# selfbus_dap_debugger.net
KiCad netlist of a schematic drawn in EAGLE
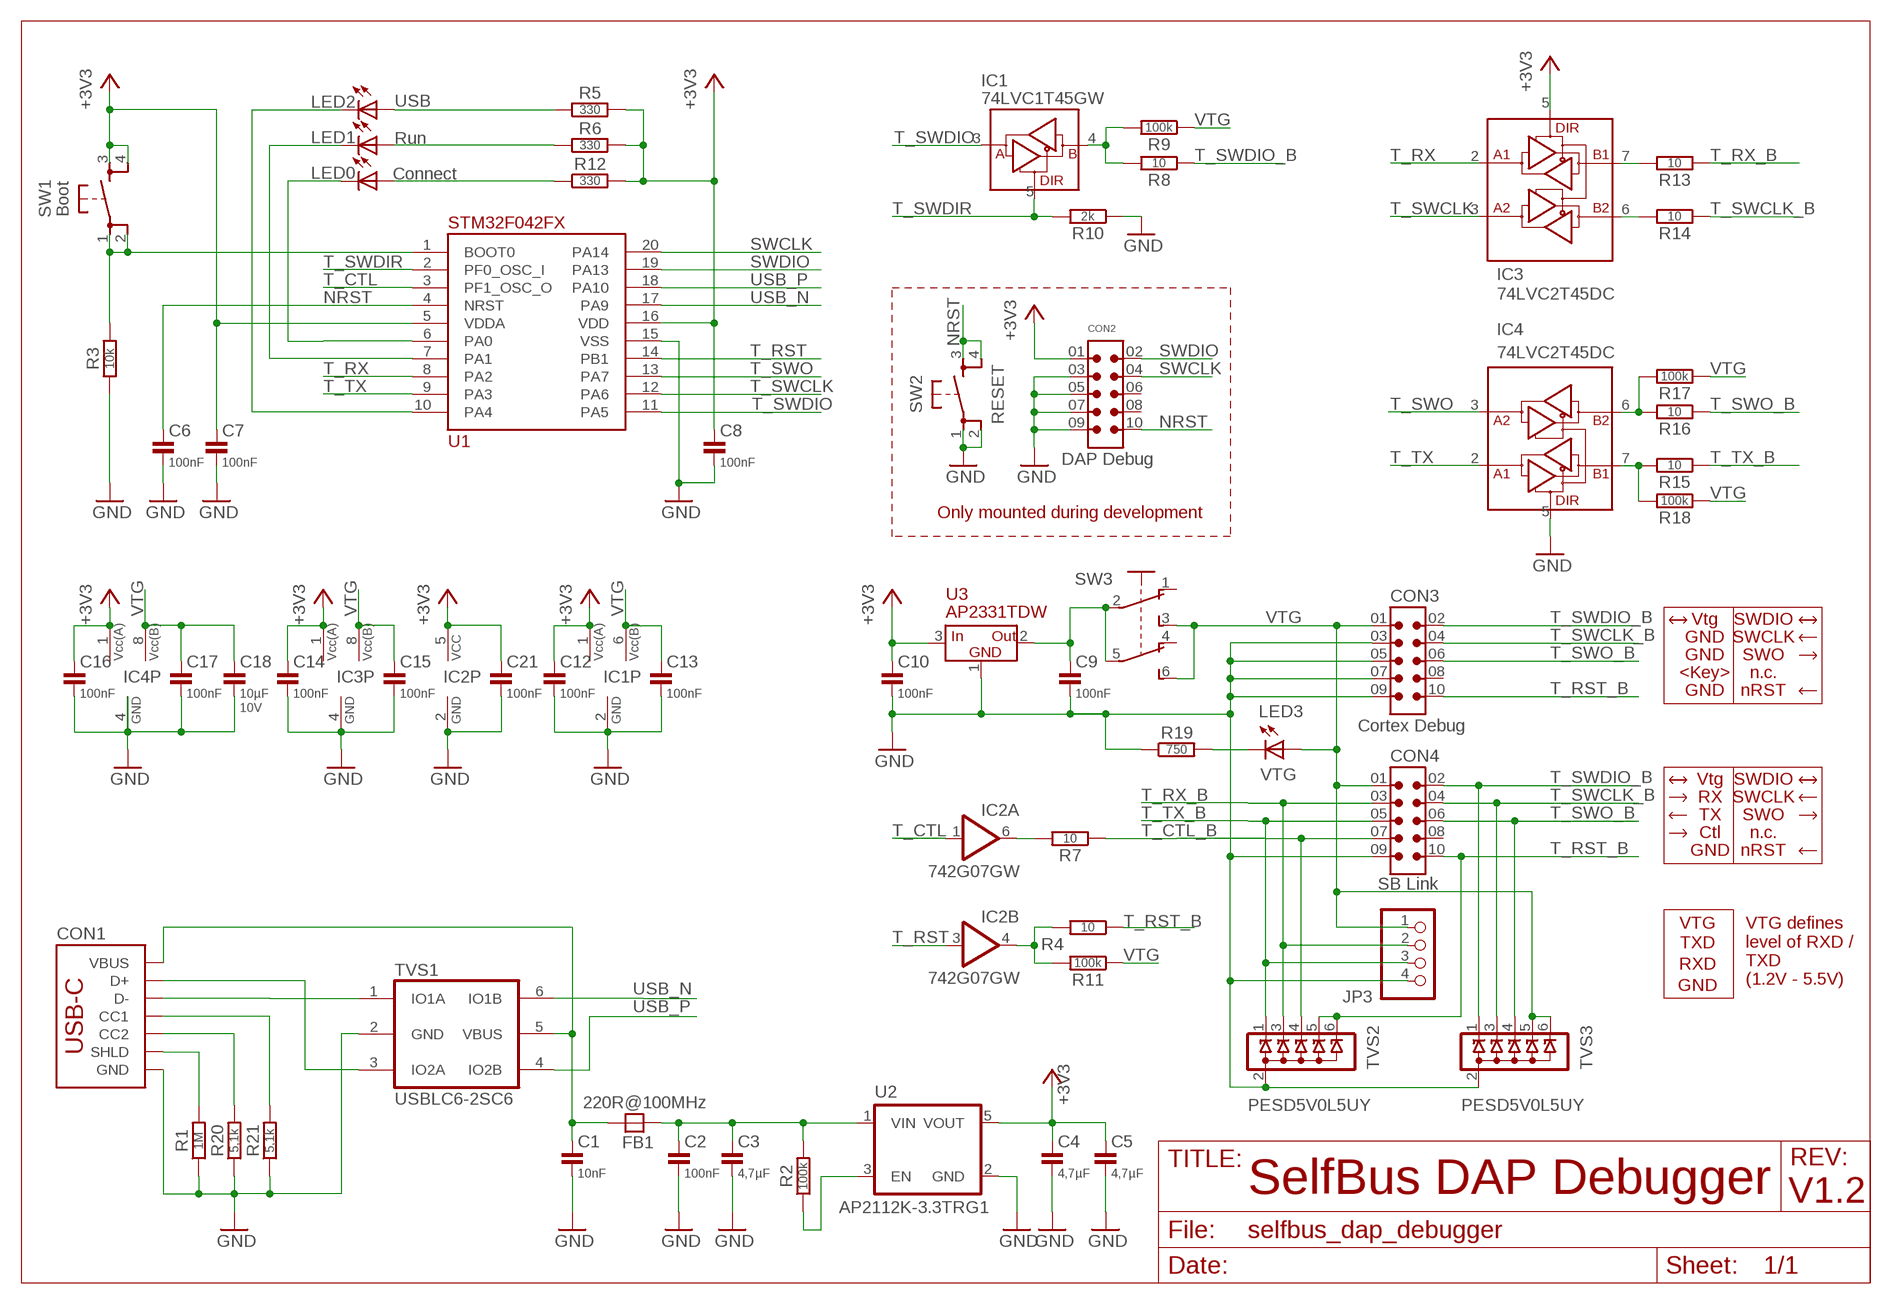
[diagram p0: schematic, sheet 1]

(export (version "E")
  (design (tool "Eeschema 10.0.6"))
  (components
    (comp (ref "C1")
      (value "10nF")
      (footprint "eagle-import:C0805")
      (libsource (lib "eagle-import") (part "C-EUC0805"))
    )
    (comp (ref "C2")
      (value "100nF")
      (footprint "eagle-import:C0805")
      (libsource (lib "eagle-import") (part "C-EUC0805"))
    )
    (comp (ref "C3")
      (value "4,7µF")
      (footprint "eagle-import:C0805")
      (libsource (lib "eagle-import") (part "C-EUC0805"))
    )
    (comp (ref "C4")
      (value "4,7µF")
      (footprint "eagle-import:C0805")
      (libsource (lib "eagle-import") (part "C-EUC0805"))
    )
    (comp (ref "C5")
      (value "4,7µF")
      (footprint "eagle-import:C0805")
      (libsource (lib "eagle-import") (part "C-EUC0805"))
    )
    (comp (ref "C6")
      (value "100nF")
      (footprint "eagle-import:C0805")
      (libsource (lib "eagle-import") (part "C-EUC0805"))
    )
    (comp (ref "C7")
      (value "100nF")
      (footprint "eagle-import:C0805")
      (libsource (lib "eagle-import") (part "C-EUC0805"))
    )
    (comp (ref "C8")
      (value "100nF")
      (footprint "eagle-import:C0805")
      (libsource (lib "eagle-import") (part "C-EUC0805"))
    )
    (comp (ref "C9")
      (value "100nF")
      (footprint "eagle-import:C0805")
      (libsource (lib "eagle-import") (part "C-EUC0805"))
    )
    (comp (ref "C10")
      (value "100nF")
      (footprint "eagle-import:C0805")
      (libsource (lib "eagle-import") (part "C-EUC0805"))
    )
    (comp (ref "C12")
      (value "100nF")
      (footprint "eagle-import:C0805")
      (libsource (lib "eagle-import") (part "C-EUC0805"))
    )
    (comp (ref "C13")
      (value "100nF")
      (footprint "eagle-import:C0805")
      (libsource (lib "eagle-import") (part "C-EUC0805"))
    )
    (comp (ref "C14")
      (value "100nF")
      (footprint "eagle-import:C0805")
      (libsource (lib "eagle-import") (part "C-EUC0805"))
    )
    (comp (ref "C15")
      (value "100nF")
      (footprint "eagle-import:C0805")
      (libsource (lib "eagle-import") (part "C-EUC0805"))
    )
    (comp (ref "C16")
      (value "100nF")
      (footprint "eagle-import:C0805")
      (libsource (lib "eagle-import") (part "C-EUC0805"))
    )
    (comp (ref "C17")
      (value "100nF")
      (footprint "eagle-import:C0805")
      (libsource (lib "eagle-import") (part "C-EUC0805"))
    )
    (comp (ref "C18")
      (value "10µF")
      (footprint "eagle-import:C0805")
      (fields (field (name "VOLTAGE") "10V"))
      (libsource (lib "eagle-import") (part "C-EUC0805"))
    )
    (comp (ref "C21")
      (value "100nF")
      (footprint "eagle-import:C0805")
      (libsource (lib "eagle-import") (part "C-EUC0805"))
    )
    (comp (ref "CON1")
      (value "XKB U262-161N-4BVC11")
      (footprint "eagle-import:USB-C-16P-2LAYER-PADS")
      (libsource (lib "eagle-import") (part "USB_C_2-LAYER_PADS"))
    )
    (comp (ref "CON2")
      (value "SHF-105-01-X-D-TH")
      (footprint "eagle-import:SAMTEC_SHF-105-01-X-D-TH")
      (libsource (lib "eagle-import") (part "SHF-105-01-X-D-TH"))
    )
    (comp (ref "CON3")
      (value "SHF-105-01-X-D-TH")
      (footprint "eagle-import:SAMTEC_SHF-105-01-X-D-TH")
      (libsource (lib "eagle-import") (part "SHF-105-01-X-D-TH"))
    )
    (comp (ref "CON4")
      (value "SAMTEC-LTMM-105-02-T-D")
      (footprint "eagle-import:SAMTEC-LTMM-105-02-T-D")
      (libsource (lib "eagle-import") (part "SAMTEC-LTMM-105-02-T-D"))
    )
    (comp (ref "FB1")
      (value "220R@100MHz")
      (footprint "eagle-import:FB0805")
      (fields (field (name "PART#") "MPZ2012S221ATD25"))
      (libsource (lib "eagle-import") (part "FB"))
    )
    (comp (ref "IC1")
      (value "74LVC1T45GW")
      (footprint "eagle-import:SOT363")
      (fields
        (field (name "LCSC#") "C478004")
        (field (name "LCSC#2") "C548484")
        (field (name "LCSC#3") "C9382")
        (field (name "MOUSER#") "771-74LVC1T45GW125")
        (field (name "MOUSER#2") "771-74LVC1T45GWQ100H")
        (field (name "MOUSER#3") "595-74LVC1T45QDCKRQ1")
        (field (name "PART#") "74LVC1T45GW,125")
        (field (name "PART#2") "74LVC1T45GW-Q100H")
        (field (name "PART#3") "SN74LVC1T45DCKR")
        (field (name "PART_MFR") "NXP")
        (field (name "PART_MFR2") "NXP")
        (field (name "PART_MFR3") "TI")
      )
      (libsource (lib "eagle-import") (part "741T45GWLVC"))
    )
    (comp (ref "IC2")
      (value "742G07GW")
      (footprint "eagle-import:SOT363")
      (fields
        (field (name "LCSC#") "C24478")
        (field (name "PART#") "74LVC2G07GW,125")
        (field (name "PART_MFR") "NXP")
      )
      (libsource (lib "eagle-import") (part "742G07GW"))
    )
    (comp (ref "IC3")
      (value "74LVC2T45DC")
      (footprint "eagle-import:VSSOP8(0.5)")
      (fields
        (field (name "LCSC#") "C15741")
        (field (name "LCSC#2") "C139524")
        (field (name "MOUSER#") "595-SN74LVC2T45DCUT")
        (field (name "MOUSER#2") "771-74LVCH2T45DC125")
        (field (name "PART#") "SN74LVC2T45DCU")
        (field (name "PART#2") "74LVCH2T45DC,125")
        (field (name "PART_MFR") "TI")
        (field (name "PART_MFR2") "NXP")
      )
      (libsource (lib "eagle-import") (part "742T45DCLVC"))
    )
    (comp (ref "IC4")
      (value "74LVC2T45DC")
      (footprint "eagle-import:VSSOP8(0.5)")
      (libsource (lib "eagle-import") (part "742T45DCLVC"))
    )
    (comp (ref "JP3")
      (value "PINHD-1X4")
      (footprint "eagle-import:1X04")
      (libsource (lib "eagle-import") (part "PINHD-1X4"))
    )
    (comp (ref "LED0")
      (value "Connect")
      (footprint "eagle-import:LED_3MM_GREEN")
      (libsource (lib "eagle-import") (part "LED_3MM(T1)_GREEN"))
    )
    (comp (ref "LED1")
      (value "Run")
      (footprint "eagle-import:LED_3MM_YELLOW")
      (libsource (lib "eagle-import") (part "LED_3MM(T1)_YELLOW"))
    )
    (comp (ref "LED2")
      (value "USB")
      (footprint "eagle-import:LED_3MM_GREEN")
      (libsource (lib "eagle-import") (part "LED_3MM(T1)_GREEN"))
    )
    (comp (ref "LED3")
      (value "VTG")
      (footprint "eagle-import:LED_3MM_RED")
      (libsource (lib "eagle-import") (part "LED_3MM(T1)_RED"))
    )
    (comp (ref "R1")
      (value "1M")
      (footprint "eagle-import:R0805")
      (libsource (lib "eagle-import") (part "R-EU_R0805"))
    )
    (comp (ref "R2")
      (value "100k")
      (footprint "eagle-import:R0805")
      (libsource (lib "eagle-import") (part "R-EU_R0805"))
    )
    (comp (ref "R3")
      (value "10k")
      (footprint "eagle-import:R0805")
      (libsource (lib "eagle-import") (part "R-EU_R0805"))
    )
    (comp (ref "R4")
      (value "10")
      (footprint "eagle-import:R0805")
      (libsource (lib "eagle-import") (part "R-EU_R0805"))
    )
    (comp (ref "R5")
      (value "330")
      (footprint "eagle-import:R0805")
      (libsource (lib "eagle-import") (part "R-EU_R0805"))
    )
    (comp (ref "R6")
      (value "330")
      (footprint "eagle-import:R0805")
      (libsource (lib "eagle-import") (part "R-EU_R0805"))
    )
    (comp (ref "R7")
      (value "10")
      (footprint "eagle-import:R0805")
      (libsource (lib "eagle-import") (part "R-EU_R0805"))
    )
    (comp (ref "R8")
      (value "10")
      (footprint "eagle-import:R0805")
      (libsource (lib "eagle-import") (part "R-EU_R0805"))
    )
    (comp (ref "R9")
      (value "100k")
      (footprint "eagle-import:R0805")
      (libsource (lib "eagle-import") (part "R-EU_R0805"))
    )
    (comp (ref "R10")
      (value "2k")
      (footprint "eagle-import:R0805")
      (libsource (lib "eagle-import") (part "R-EU_R0805"))
    )
    (comp (ref "R11")
      (value "100k")
      (footprint "eagle-import:R0805")
      (libsource (lib "eagle-import") (part "R-EU_R0805"))
    )
    (comp (ref "R12")
      (value "330")
      (footprint "eagle-import:R0805")
      (libsource (lib "eagle-import") (part "R-EU_R0805"))
    )
    (comp (ref "R13")
      (value "10")
      (footprint "eagle-import:R0805")
      (libsource (lib "eagle-import") (part "R-EU_R0805"))
    )
    (comp (ref "R14")
      (value "10")
      (footprint "eagle-import:R0805")
      (libsource (lib "eagle-import") (part "R-EU_R0805"))
    )
    (comp (ref "R15")
      (value "10")
      (footprint "eagle-import:R0805")
      (libsource (lib "eagle-import") (part "R-EU_R0805"))
    )
    (comp (ref "R16")
      (value "10")
      (footprint "eagle-import:R0805")
      (libsource (lib "eagle-import") (part "R-EU_R0805"))
    )
    (comp (ref "R17")
      (value "100k")
      (footprint "eagle-import:R0805")
      (libsource (lib "eagle-import") (part "R-EU_R0805"))
    )
    (comp (ref "R18")
      (value "100k")
      (footprint "eagle-import:R0805")
      (libsource (lib "eagle-import") (part "R-EU_R0805"))
    )
    (comp (ref "R19")
      (value "750")
      (footprint "eagle-import:R0805")
      (libsource (lib "eagle-import") (part "R-EU_R0805"))
    )
    (comp (ref "R20")
      (value "5,1k")
      (footprint "eagle-import:R0805")
      (libsource (lib "eagle-import") (part "R-EU_R0805"))
    )
    (comp (ref "R21")
      (value "5,1k")
      (footprint "eagle-import:R0805")
      (libsource (lib "eagle-import") (part "R-EU_R0805"))
    )
    (comp (ref "SW1")
      (value "BOOT")
      (footprint "eagle-import:TACT_SWITCH_6X6_SNAP-IN_17")
      (fields (field (name "PART#") "SKHHDHA010"))
      (libsource (lib "eagle-import") (part "ALPS_SKHHDHA010"))
    )
    (comp (ref "SW2")
      (value "RESET")
      (footprint "eagle-import:TACT_SWITCH_6X6_SNAP-IN_17")
      (fields (field (name "PART#") "SKHHDHA010"))
      (libsource (lib "eagle-import") (part "ALPS_SKHHDHA010"))
    )
    (comp (ref "SW3")
      (value "XKB7070-Z")
      (footprint "eagle-import:XKB7070")
      (libsource (lib "eagle-import") (part "XKB7070-Z"))
    )
    (comp (ref "TVS1")
      (value "USBLC6-2SC6")
      (footprint "eagle-import:SOT-23-6L")
      (libsource (lib "eagle-import") (part "USBLC6-2SC6"))
    )
    (comp (ref "TVS2")
      (value "PESD5V0L5UY")
      (footprint "eagle-import:SOT363")
      (libsource (lib "eagle-import") (part "PESD5V0L5UY"))
    )
    (comp (ref "TVS3")
      (value "PESD5V0L5UY")
      (footprint "eagle-import:SOT363")
      (libsource (lib "eagle-import") (part "PESD5V0L5UY"))
    )
    (comp (ref "U1")
      (value "STM32F042FX")
      (footprint "eagle-import:TSSOP20")
      (fields (field (name "PART#") "STM32F042F4P6"))
      (libsource (lib "eagle-import") (part "STM32F042FX"))
    )
    (comp (ref "U2")
      (value "AP2112K-3.3TRG1")
      (footprint "eagle-import:SOT23-5")
      (libsource (lib "eagle-import") (part "AP2112K-3.3TRG1"))
    )
    (comp (ref "U3")
      (value "AP2331TDW")
      (footprint "eagle-import:SC59")
      (fields (field (name "PART#") "AP2331W-7"))
      (libsource (lib "eagle-import") (part "AP2331TDW"))
    )
  )
  (nets
    (net (code "1") (name "+3V3") (class "Default")
      (node (ref "C10") (pin "1") (pinfunction "1_1") (pintype "passive"))
      (node (ref "C12") (pin "1") (pinfunction "1_1") (pintype "passive"))
      (node (ref "C14") (pin "1") (pinfunction "1_1") (pintype "passive"))
      (node (ref "C16") (pin "1") (pinfunction "1_1") (pintype "passive"))
      (node (ref "C21") (pin "1") (pinfunction "1_1") (pintype "passive"))
      (node (ref "C4") (pin "1") (pinfunction "1_1") (pintype "passive"))
      (node (ref "C5") (pin "1") (pinfunction "1_1") (pintype "passive"))
      (node (ref "C7") (pin "1") (pinfunction "1_1") (pintype "passive"))
      (node (ref "C8") (pin "1") (pinfunction "1_1") (pintype "passive"))
      (node (ref "CON2") (pin "01") (pinfunction "1_01") (pintype "passive"))
      (node (ref "IC1") (pin "1") (pinfunction "VCC(A)_1") (pintype "power_in"))
      (node (ref "IC2") (pin "5") (pinfunction "VCC_5") (pintype "power_in"))
      (node (ref "IC3") (pin "1") (pinfunction "VCC(A)_1") (pintype "power_in"))
      (node (ref "IC3") (pin "5") (pinfunction "DIR_5") (pintype "input"))
      (node (ref "IC4") (pin "1") (pinfunction "VCC(A)_1") (pintype "power_in"))
      (node (ref "R12") (pin "2") (pinfunction "2_2") (pintype "passive"))
      (node (ref "R5") (pin "2") (pinfunction "2_2") (pintype "passive"))
      (node (ref "R6") (pin "2") (pinfunction "2_2") (pintype "passive"))
      (node (ref "SW1") (pin "3") (pinfunction "3_3") (pintype "passive"))
      (node (ref "SW1") (pin "4") (pinfunction "4_4") (pintype "passive"))
      (node (ref "U1") (pin "16") (pinfunction "VDD_16") (pintype "power_in"))
      (node (ref "U1") (pin "5") (pinfunction "VDDA_5") (pintype "power_in"))
      (node (ref "U2") (pin "5") (pinfunction "VOUT_5") (pintype "passive"))
      (node (ref "U3") (pin "3") (pinfunction "IN_3") (pintype "bidirectional"))
    )
    (net (code "2") (name "/NRST") (class "Default")
      (node (ref "C6") (pin "1") (pinfunction "1_1") (pintype "passive"))
      (node (ref "CON2") (pin "10") (pinfunction "10_10") (pintype "passive"))
      (node (ref "SW2") (pin "3") (pinfunction "3_3") (pintype "passive"))
      (node (ref "SW2") (pin "4") (pinfunction "4_4") (pintype "passive"))
      (node (ref "U1") (pin "4") (pinfunction "NRST_4") (pintype "input"))
    )
    (net (code "3") (name "/SWCLK") (class "Default")
      (node (ref "CON2") (pin "04") (pinfunction "4_04") (pintype "passive"))
      (node (ref "U1") (pin "20") (pinfunction "PA14_20") (pintype "bidirectional"))
    )
    (net (code "4") (name "/SWDIO") (class "Default")
      (node (ref "CON2") (pin "02") (pinfunction "2_02") (pintype "passive"))
      (node (ref "U1") (pin "19") (pinfunction "PA13_19") (pintype "bidirectional"))
    )
    (net (code "5") (name "/T_CTL") (class "Default")
      (node (ref "IC2") (pin "1") (pinfunction "IN_1") (pintype "input"))
      (node (ref "U1") (pin "3") (pinfunction "PF1_OSC_O_3") (pintype "bidirectional"))
    )
    (net (code "6") (name "/T_CTL_B") (class "Default")
      (node (ref "CON4") (pin "07") (pinfunction "7_07") (pintype "passive"))
      (node (ref "R7") (pin "1") (pinfunction "1_1") (pintype "passive"))
      (node (ref "TVS2") (pin "4") (pinfunction "C3_4") (pintype "passive"))
    )
    (net (code "7") (name "/T_RST") (class "Default")
      (node (ref "IC2") (pin "3") (pinfunction "IN_3") (pintype "input"))
      (node (ref "U1") (pin "14") (pinfunction "PB1_14") (pintype "bidirectional"))
    )
    (net (code "8") (name "/T_RST_B") (class "Default")
      (node (ref "CON3") (pin "10") (pinfunction "10_10") (pintype "passive"))
      (node (ref "CON4") (pin "10") (pinfunction "10_10") (pintype "passive"))
      (node (ref "R4") (pin "1") (pinfunction "1_1") (pintype "passive"))
      (node (ref "TVS2") (pin "5") (pinfunction "C4_5") (pintype "passive"))
      (node (ref "TVS2") (pin "6") (pinfunction "C5_6") (pintype "passive"))
    )
    (net (code "9") (name "/T_RX") (class "Default")
      (node (ref "IC3") (pin "2") (pinfunction "A1_2") (pintype "bidirectional"))
      (node (ref "U1") (pin "8") (pinfunction "PA2_8") (pintype "bidirectional"))
    )
    (net (code "10") (name "/T_RX_B") (class "Default")
      (node (ref "CON4") (pin "03") (pinfunction "3_03") (pintype "passive"))
      (node (ref "JP3") (pin "2") (pinfunction "2_2") (pintype "passive"))
      (node (ref "R13") (pin "1") (pinfunction "1_1") (pintype "passive"))
      (node (ref "TVS2") (pin "3") (pinfunction "C2_3") (pintype "passive"))
    )
    (net (code "11") (name "/T_SWCLK") (class "Default")
      (node (ref "IC3") (pin "3") (pinfunction "A2_3") (pintype "bidirectional"))
      (node (ref "U1") (pin "12") (pinfunction "PA6_12") (pintype "bidirectional"))
    )
    (net (code "12") (name "/T_SWCLK_B") (class "Default")
      (node (ref "CON3") (pin "04") (pinfunction "4_04") (pintype "passive"))
      (node (ref "CON4") (pin "04") (pinfunction "4_04") (pintype "passive"))
      (node (ref "R14") (pin "1") (pinfunction "1_1") (pintype "passive"))
      (node (ref "TVS3") (pin "3") (pinfunction "C2_3") (pintype "passive"))
    )
    (net (code "13") (name "/T_SWDIO") (class "Default")
      (node (ref "IC1") (pin "3") (pinfunction "A_3") (pintype "bidirectional"))
      (node (ref "U1") (pin "11") (pinfunction "PA5_11") (pintype "bidirectional"))
    )
    (net (code "14") (name "/T_SWDIO_B") (class "Default")
      (node (ref "CON3") (pin "02") (pinfunction "2_02") (pintype "passive"))
      (node (ref "CON4") (pin "02") (pinfunction "2_02") (pintype "passive"))
      (node (ref "R8") (pin "1") (pinfunction "1_1") (pintype "passive"))
      (node (ref "TVS3") (pin "1") (pinfunction "C1_1") (pintype "passive"))
    )
    (net (code "15") (name "/T_SWDIR") (class "Default")
      (node (ref "IC1") (pin "5") (pinfunction "DIR_5") (pintype "input"))
      (node (ref "R10") (pin "2") (pinfunction "2_2") (pintype "passive"))
      (node (ref "U1") (pin "2") (pinfunction "PF0_OSC_I_2") (pintype "bidirectional"))
    )
    (net (code "16") (name "/T_SWO") (class "Default")
      (node (ref "IC4") (pin "3") (pinfunction "A2_3") (pintype "bidirectional"))
      (node (ref "U1") (pin "13") (pinfunction "PA7_13") (pintype "bidirectional"))
    )
    (net (code "17") (name "/T_SWO_B") (class "Default")
      (node (ref "CON3") (pin "06") (pinfunction "6_06") (pintype "passive"))
      (node (ref "CON4") (pin "06") (pinfunction "6_06") (pintype "passive"))
      (node (ref "R16") (pin "1") (pinfunction "1_1") (pintype "passive"))
      (node (ref "TVS3") (pin "4") (pinfunction "C3_4") (pintype "passive"))
    )
    (net (code "18") (name "/T_TX") (class "Default")
      (node (ref "IC4") (pin "2") (pinfunction "A1_2") (pintype "bidirectional"))
      (node (ref "U1") (pin "9") (pinfunction "PA3_9") (pintype "bidirectional"))
    )
    (net (code "19") (name "/T_TX_B") (class "Default")
      (node (ref "CON4") (pin "05") (pinfunction "5_05") (pintype "passive"))
      (node (ref "JP3") (pin "3") (pinfunction "3_3") (pintype "passive"))
      (node (ref "R15") (pin "1") (pinfunction "1_1") (pintype "passive"))
      (node (ref "TVS2") (pin "1") (pinfunction "C1_1") (pintype "passive"))
    )
    (net (code "20") (name "/USB_N") (class "Default")
      (node (ref "TVS1") (pin "6") (pinfunction "IO1B_6") (pintype "bidirectional"))
      (node (ref "U1") (pin "17") (pinfunction "PA9_17") (pintype "bidirectional"))
    )
    (net (code "21") (name "/USB_P") (class "Default")
      (node (ref "TVS1") (pin "4") (pinfunction "IO2B_4") (pintype "bidirectional"))
      (node (ref "U1") (pin "18") (pinfunction "PA10_18") (pintype "bidirectional"))
    )
    (net (code "22") (name "/VTG") (class "Default")
      (node (ref "C13") (pin "1") (pinfunction "1_1") (pintype "passive"))
      (node (ref "C15") (pin "1") (pinfunction "1_1") (pintype "passive"))
      (node (ref "C17") (pin "1") (pinfunction "1_1") (pintype "passive"))
      (node (ref "C18") (pin "1") (pinfunction "1_1") (pintype "passive"))
      (node (ref "CON3") (pin "01") (pinfunction "1_01") (pintype "passive"))
      (node (ref "CON4") (pin "01") (pinfunction "1_01") (pintype "passive"))
      (node (ref "IC1") (pin "6") (pinfunction "VCC(B)_6") (pintype "power_in"))
      (node (ref "IC3") (pin "8") (pinfunction "VCC(B)_8") (pintype "power_in"))
      (node (ref "IC4") (pin "8") (pinfunction "VCC(B)_8") (pintype "power_in"))
      (node (ref "JP3") (pin "1") (pinfunction "1_1") (pintype "passive"))
      (node (ref "LED3") (pin "A") (pinfunction "A_A") (pintype "passive"))
      (node (ref "R11") (pin "1") (pinfunction "1_1") (pintype "passive"))
      (node (ref "R17") (pin "1") (pinfunction "1_1") (pintype "passive"))
      (node (ref "R18") (pin "1") (pinfunction "1_1") (pintype "passive"))
      (node (ref "R9") (pin "1") (pinfunction "1_1") (pintype "passive"))
      (node (ref "SW3") (pin "3") (pinfunction "S_3") (pintype "passive"))
      (node (ref "SW3") (pin "6") (pinfunction "S_6") (pintype "passive"))
      (node (ref "TVS3") (pin "5") (pinfunction "C4_5") (pintype "passive"))
      (node (ref "TVS3") (pin "6") (pinfunction "C5_6") (pintype "passive"))
    )
    (net (code "23") (name "GND") (class "Default")
      (node (ref "C1") (pin "2") (pinfunction "2_2") (pintype "passive"))
      (node (ref "C10") (pin "2") (pinfunction "2_2") (pintype "passive"))
      (node (ref "C12") (pin "2") (pinfunction "2_2") (pintype "passive"))
      (node (ref "C13") (pin "2") (pinfunction "2_2") (pintype "passive"))
      (node (ref "C14") (pin "2") (pinfunction "2_2") (pintype "passive"))
      (node (ref "C15") (pin "2") (pinfunction "2_2") (pintype "passive"))
      (node (ref "C16") (pin "2") (pinfunction "2_2") (pintype "passive"))
      (node (ref "C17") (pin "2") (pinfunction "2_2") (pintype "passive"))
      (node (ref "C18") (pin "2") (pinfunction "2_2") (pintype "passive"))
      (node (ref "C2") (pin "2") (pinfunction "2_2") (pintype "passive"))
      (node (ref "C21") (pin "2") (pinfunction "2_2") (pintype "passive"))
      (node (ref "C3") (pin "2") (pinfunction "2_2") (pintype "passive"))
      (node (ref "C4") (pin "2") (pinfunction "2_2") (pintype "passive"))
      (node (ref "C5") (pin "2") (pinfunction "2_2") (pintype "passive"))
      (node (ref "C6") (pin "2") (pinfunction "2_2") (pintype "passive"))
      (node (ref "C7") (pin "2") (pinfunction "2_2") (pintype "passive"))
      (node (ref "C8") (pin "2") (pinfunction "2_2") (pintype "passive"))
      (node (ref "C9") (pin "2") (pinfunction "2_2") (pintype "passive"))
      (node (ref "CON1") (pin "GND") (pinfunction "GND_GND") (pintype "bidirectional"))
      (node (ref "CON1") (pin "GND2") (pinfunction "GND_GND2") (pintype "bidirectional"))
      (node (ref "CON2") (pin "03") (pinfunction "3_03") (pintype "passive"))
      (node (ref "CON2") (pin "05") (pinfunction "5_05") (pintype "passive"))
      (node (ref "CON2") (pin "07") (pinfunction "7_07") (pintype "passive"))
      (node (ref "CON2") (pin "09") (pinfunction "9_09") (pintype "passive"))
      (node (ref "CON3") (pin "03") (pinfunction "3_03") (pintype "passive"))
      (node (ref "CON3") (pin "05") (pinfunction "5_05") (pintype "passive"))
      (node (ref "CON3") (pin "07") (pinfunction "7_07") (pintype "passive"))
      (node (ref "CON3") (pin "09") (pinfunction "9_09") (pintype "passive"))
      (node (ref "CON4") (pin "09") (pinfunction "9_09") (pintype "passive"))
      (node (ref "IC1") (pin "2") (pinfunction "GND_2") (pintype "power_in"))
      (node (ref "IC2") (pin "2") (pinfunction "GND_2") (pintype "power_in"))
      (node (ref "IC3") (pin "4") (pinfunction "GND_4") (pintype "power_in"))
      (node (ref "IC4") (pin "4") (pinfunction "GND_4") (pintype "power_in"))
      (node (ref "IC4") (pin "5") (pinfunction "DIR_5") (pintype "input"))
      (node (ref "JP3") (pin "4") (pinfunction "4_4") (pintype "passive"))
      (node (ref "R1") (pin "1") (pinfunction "1_1") (pintype "passive"))
      (node (ref "R10") (pin "1") (pinfunction "1_1") (pintype "passive"))
      (node (ref "R19") (pin "1") (pinfunction "1_1") (pintype "passive"))
      (node (ref "R20") (pin "1") (pinfunction "1_1") (pintype "passive"))
      (node (ref "R21") (pin "1") (pinfunction "1_1") (pintype "passive"))
      (node (ref "R3") (pin "1") (pinfunction "1_1") (pintype "passive"))
      (node (ref "SW2") (pin "1") (pinfunction "1_1") (pintype "passive"))
      (node (ref "SW2") (pin "2") (pinfunction "2_2") (pintype "passive"))
      (node (ref "TVS1") (pin "2") (pinfunction "GND_2") (pintype "bidirectional"))
      (node (ref "TVS2") (pin "2") (pinfunction "A_2") (pintype "passive"))
      (node (ref "TVS3") (pin "2") (pinfunction "A_2") (pintype "passive"))
      (node (ref "U1") (pin "15") (pinfunction "VSS_15") (pintype "power_in"))
      (node (ref "U2") (pin "2") (pinfunction "GND_2") (pintype "input"))
      (node (ref "U3") (pin "1") (pinfunction "GND_1") (pintype "bidirectional"))
    )
    (net (code "24") (name "Net-(CON1-CC1)") (class "Default")
      (node (ref "CON1") (pin "A5") (pinfunction "CC1_A5") (pintype "bidirectional"))
      (node (ref "R21") (pin "2") (pinfunction "2_2") (pintype "passive"))
    )
    (net (code "25") (name "Net-(CON1-CC2)") (class "Default")
      (node (ref "CON1") (pin "B5") (pinfunction "CC2_B5") (pintype "bidirectional"))
      (node (ref "R20") (pin "2") (pinfunction "2_2") (pintype "passive"))
    )
    (net (code "26") (name "Net-(CON1-SHLD-PadSHLD1)") (class "Default")
      (node (ref "CON1") (pin "SHLD1") (pinfunction "SHLD_SHLD1") (pintype "bidirectional"))
      (node (ref "CON1") (pin "SHLD2") (pinfunction "SHLD_SHLD2") (pintype "bidirectional"))
      (node (ref "CON1") (pin "SHLD3") (pinfunction "SHLD_SHLD3") (pintype "bidirectional"))
      (node (ref "CON1") (pin "SHLD4") (pinfunction "SHLD_SHLD4") (pintype "bidirectional"))
      (node (ref "R1") (pin "2") (pinfunction "2_2") (pintype "passive"))
    )
    (net (code "27") (name "Net-(IC1A-B)") (class "Default")
      (node (ref "IC1") (pin "4") (pinfunction "B_4") (pintype "tri_state"))
      (node (ref "R8") (pin "2") (pinfunction "2_2") (pintype "passive"))
      (node (ref "R9") (pin "2") (pinfunction "2_2") (pintype "passive"))
    )
    (net (code "28") (name "Net-(IC2A-OUT)") (class "Default")
      (node (ref "IC2") (pin "6") (pinfunction "OUT_6") (pintype "open_collector"))
      (node (ref "R7") (pin "2") (pinfunction "2_2") (pintype "passive"))
    )
    (net (code "29") (name "Net-(IC2B-OUT)") (class "Default")
      (node (ref "IC2") (pin "4") (pinfunction "OUT_4") (pintype "open_collector"))
      (node (ref "R11") (pin "2") (pinfunction "2_2") (pintype "passive"))
      (node (ref "R4") (pin "2") (pinfunction "2_2") (pintype "passive"))
    )
    (net (code "30") (name "Net-(IC3A-B1)") (class "Default")
      (node (ref "IC3") (pin "7") (pinfunction "B1_7") (pintype "tri_state"))
      (node (ref "R13") (pin "2") (pinfunction "2_2") (pintype "passive"))
    )
    (net (code "31") (name "Net-(IC3A-B2)") (class "Default")
      (node (ref "IC3") (pin "6") (pinfunction "B2_6") (pintype "tri_state"))
      (node (ref "R14") (pin "2") (pinfunction "2_2") (pintype "passive"))
    )
    (net (code "32") (name "Net-(IC4A-B1)") (class "Default")
      (node (ref "IC4") (pin "7") (pinfunction "B1_7") (pintype "tri_state"))
      (node (ref "R15") (pin "2") (pinfunction "2_2") (pintype "passive"))
      (node (ref "R18") (pin "2") (pinfunction "2_2") (pintype "passive"))
    )
    (net (code "33") (name "Net-(IC4A-B2)") (class "Default")
      (node (ref "IC4") (pin "6") (pinfunction "B2_6") (pintype "tri_state"))
      (node (ref "R16") (pin "2") (pinfunction "2_2") (pintype "passive"))
      (node (ref "R17") (pin "2") (pinfunction "2_2") (pintype "passive"))
    )
    (net (code "34") (name "Net-(LED0-PadA)") (class "Default")
      (node (ref "LED0") (pin "A") (pinfunction "A_A") (pintype "passive"))
      (node (ref "R12") (pin "1") (pinfunction "1_1") (pintype "passive"))
    )
    (net (code "35") (name "Net-(LED1-PadA)") (class "Default")
      (node (ref "LED1") (pin "A") (pinfunction "A_A") (pintype "passive"))
      (node (ref "R6") (pin "1") (pinfunction "1_1") (pintype "passive"))
    )
    (net (code "36") (name "Net-(LED2-PadA)") (class "Default")
      (node (ref "LED2") (pin "A") (pinfunction "A_A") (pintype "passive"))
      (node (ref "R5") (pin "1") (pinfunction "1_1") (pintype "passive"))
    )
    (net (code "37") (name "Net-(LED3-PadC)") (class "Default")
      (node (ref "LED3") (pin "C") (pinfunction "C_C") (pintype "passive"))
      (node (ref "R19") (pin "2") (pinfunction "2_2") (pintype "passive"))
    )
    (net (code "38") (name "Net-(SW3A-P)") (class "Default")
      (node (ref "C9") (pin "1") (pinfunction "1_1") (pintype "passive"))
      (node (ref "SW3") (pin "2") (pinfunction "P_2") (pintype "passive"))
      (node (ref "SW3") (pin "5") (pinfunction "P_5") (pintype "passive"))
      (node (ref "U3") (pin "2") (pinfunction "OUT_2") (pintype "bidirectional"))
    )
    (net (code "39") (name "Net-(TVS1-IO1A)") (class "Default")
      (node (ref "CON1") (pin "A7") (pinfunction "D-_A7") (pintype "bidirectional"))
      (node (ref "CON1") (pin "B7") (pinfunction "D-_B7") (pintype "bidirectional"))
      (node (ref "TVS1") (pin "1") (pinfunction "IO1A_1") (pintype "bidirectional"))
    )
    (net (code "40") (name "Net-(TVS1-IO2A)") (class "Default")
      (node (ref "CON1") (pin "A6") (pinfunction "D+_A6") (pintype "bidirectional"))
      (node (ref "CON1") (pin "B6") (pinfunction "D+_B6") (pintype "bidirectional"))
      (node (ref "TVS1") (pin "3") (pinfunction "IO2A_3") (pintype "bidirectional"))
    )
    (net (code "41") (name "Net-(TVS1-VBUS)") (class "Default")
      (node (ref "C1") (pin "1") (pinfunction "1_1") (pintype "passive"))
      (node (ref "CON1") (pin "VBUS1") (pinfunction "VBUS_VBUS1") (pintype "bidirectional"))
      (node (ref "CON1") (pin "VBUS2") (pinfunction "VBUS_VBUS2") (pintype "bidirectional"))
      (node (ref "FB1") (pin "1") (pinfunction "1_1") (pintype "passive"))
      (node (ref "TVS1") (pin "5") (pinfunction "VBUS_5") (pintype "bidirectional"))
    )
    (net (code "42") (name "Net-(U1-BOOT0)") (class "Default")
      (node (ref "R3") (pin "2") (pinfunction "2_2") (pintype "passive"))
      (node (ref "SW1") (pin "1") (pinfunction "1_1") (pintype "passive"))
      (node (ref "SW1") (pin "2") (pinfunction "2_2") (pintype "passive"))
      (node (ref "U1") (pin "1") (pinfunction "BOOT0_1") (pintype "bidirectional"))
    )
    (net (code "43") (name "Net-(U1-PA0)") (class "Default")
      (node (ref "LED0") (pin "C") (pinfunction "C_C") (pintype "passive"))
      (node (ref "U1") (pin "6") (pinfunction "PA0_6") (pintype "bidirectional"))
    )
    (net (code "44") (name "Net-(U1-PA1)") (class "Default")
      (node (ref "LED1") (pin "C") (pinfunction "C_C") (pintype "passive"))
      (node (ref "U1") (pin "7") (pinfunction "PA1_7") (pintype "bidirectional"))
    )
    (net (code "45") (name "Net-(U1-PA4)") (class "Default")
      (node (ref "LED2") (pin "C") (pinfunction "C_C") (pintype "passive"))
      (node (ref "U1") (pin "10") (pinfunction "PA4_10") (pintype "bidirectional"))
    )
    (net (code "46") (name "Net-(U2-EN)") (class "Default")
      (node (ref "R2") (pin "1") (pinfunction "1_1") (pintype "passive"))
      (node (ref "U2") (pin "3") (pinfunction "EN_3") (pintype "input"))
    )
    (net (code "47") (name "Net-(U2-VIN)") (class "Default")
      (node (ref "C2") (pin "1") (pinfunction "1_1") (pintype "passive"))
      (node (ref "C3") (pin "1") (pinfunction "1_1") (pintype "passive"))
      (node (ref "FB1") (pin "2") (pinfunction "2_2") (pintype "passive"))
      (node (ref "R2") (pin "2") (pinfunction "2_2") (pintype "passive"))
      (node (ref "U2") (pin "1") (pinfunction "VIN_1") (pintype "input"))
    )
    (net (code "48") (name "unconnected-(CON2-6-Pad06)") (class "Default")
      (node (ref "CON2") (pin "06") (pinfunction "6_06") (pintype "passive"))
    )
    (net (code "49") (name "unconnected-(CON2-8-Pad08)") (class "Default")
      (node (ref "CON2") (pin "08") (pinfunction "8_08") (pintype "passive"))
    )
    (net (code "50") (name "unconnected-(CON3-8-Pad08)") (class "Default")
      (node (ref "CON3") (pin "08") (pinfunction "8_08") (pintype "passive"))
    )
    (net (code "51") (name "unconnected-(CON4-8-Pad08)") (class "Default")
      (node (ref "CON4") (pin "08") (pinfunction "8_08") (pintype "passive"))
    )
    (net (code "52") (name "unconnected-(SW3A-O-Pad1)") (class "Default")
      (node (ref "SW3") (pin "1") (pinfunction "O_1") (pintype "passive"))
    )
    (net (code "53") (name "unconnected-(SW3B-O-Pad4)") (class "Default")
      (node (ref "SW3") (pin "4") (pinfunction "O_4") (pintype "passive"))
    )
  )
)
